# cableVGA.net
KiCad netlist of a schematic drawn in EAGLE
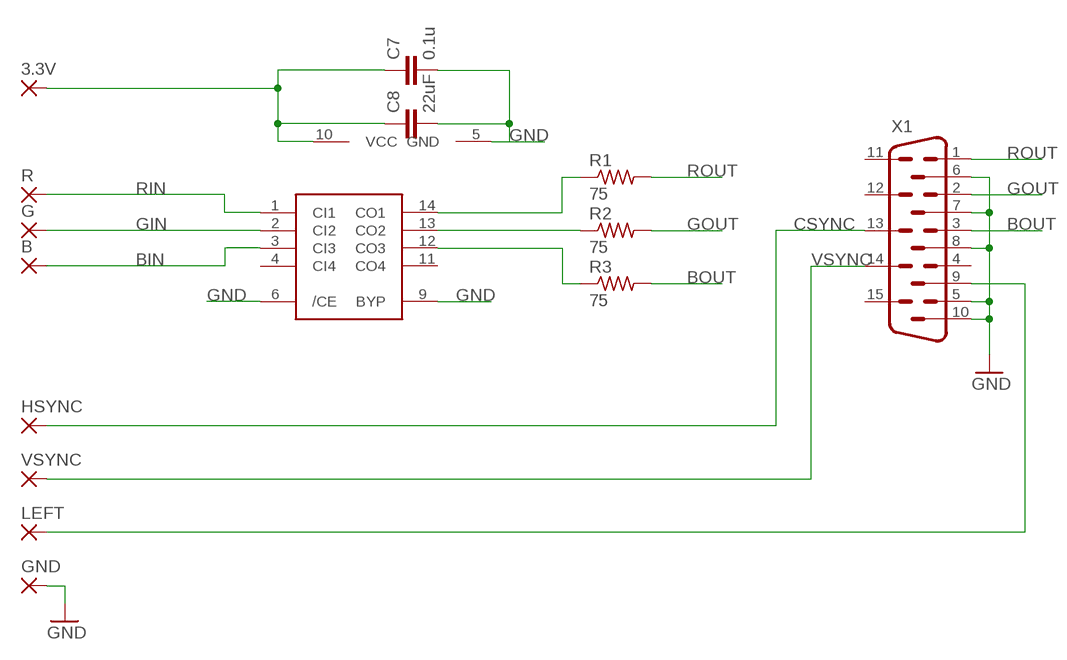
[diagram p0: schematic, sheet 1]

(export (version "E")
  (design (tool "Eeschema 10.0.6"))
  (components
    (comp (ref "3.3V")
      (value "WIREPADSMD2,54-5,08")
      (footprint "eagle-import:SMD2,54-5,08")
      (libsource (lib "eagle-import") (part "WIREPADSMD2,54-5,08"))
    )
    (comp (ref "B")
      (value "WIREPADSMD2,54-5,08")
      (footprint "eagle-import:SMD2,54-5,08")
      (libsource (lib "eagle-import") (part "WIREPADSMD2,54-5,08"))
    )
    (comp (ref "C7")
      (value "0.1u")
      (footprint "eagle-import:C0805K")
      (libsource (lib "eagle-import") (part "C-EUC0805K"))
    )
    (comp (ref "C8")
      (value "22uF")
      (footprint "eagle-import:C0805K")
      (libsource (lib "eagle-import") (part "C-EUC0805K"))
    )
    (comp (ref "G")
      (value "WIREPADSMD2,54-5,08")
      (footprint "eagle-import:SMD2,54-5,08")
      (libsource (lib "eagle-import") (part "WIREPADSMD2,54-5,08"))
    )
    (comp (ref "GND")
      (value "WIREPADSMD2,54-5,08")
      (footprint "eagle-import:SMD2,54-5,08")
      (libsource (lib "eagle-import") (part "WIREPADSMD2,54-5,08"))
    )
    (comp (ref "HSYNC")
      (value "WIREPADSMD2,54-5,08")
      (footprint "eagle-import:SMD2,54-5,08")
      (libsource (lib "eagle-import") (part "WIREPADSMD2,54-5,08"))
    )
    (comp (ref "LEFT")
      (value "WIREPADSMD2,54-5,08")
      (footprint "eagle-import:SMD2,54-5,08")
      (libsource (lib "eagle-import") (part "WIREPADSMD2,54-5,08"))
    )
    (comp (ref "R")
      (value "WIREPADSMD2,54-5,08")
      (footprint "eagle-import:SMD2,54-5,08")
      (libsource (lib "eagle-import") (part "WIREPADSMD2,54-5,08"))
    )
    (comp (ref "R1")
      (value "75")
      (footprint "eagle-import:R0805")
      (libsource (lib "eagle-import") (part "R-US_R0805"))
    )
    (comp (ref "R2")
      (value "75")
      (footprint "eagle-import:R0805")
      (libsource (lib "eagle-import") (part "R-US_R0805"))
    )
    (comp (ref "R3")
      (value "75")
      (footprint "eagle-import:R0805")
      (libsource (lib "eagle-import") (part "R-US_R0805"))
    )
    (comp (ref "U$2")
      (value "THS7374")
      (footprint "eagle-import:THS7374")
      (libsource (lib "eagle-import") (part "THS7374"))
    )
    (comp (ref "VSYNC")
      (value "WIREPADSMD2,54-5,08")
      (footprint "eagle-import:SMD2,54-5,08")
      (libsource (lib "eagle-import") (part "WIREPADSMD2,54-5,08"))
    )
    (comp (ref "X1")
      (value "HM15H")
      (footprint "eagle-import:HDM15H")
      (libsource (lib "eagle-import") (part "HM15H"))
    )
  )
  (nets
    (net (code "1") (name "/BIN") (class "Default")
      (node (ref "B") (pin "1") (pinfunction "P_1") (pintype "passive"))
      (node (ref "U$2") (pin "3") (pinfunction "CI3_3") (pintype "bidirectional"))
    )
    (net (code "2") (name "/BOUT") (class "Default")
      (node (ref "R3") (pin "2") (pinfunction "2_2") (pintype "passive"))
      (node (ref "X1") (pin "3") (pinfunction "3_3") (pintype "passive"))
    )
    (net (code "3") (name "/CSYNC") (class "Default")
      (node (ref "HSYNC") (pin "1") (pinfunction "P_1") (pintype "passive"))
      (node (ref "X1") (pin "13") (pinfunction "13_13") (pintype "passive"))
    )
    (net (code "4") (name "/GIN") (class "Default")
      (node (ref "G") (pin "1") (pinfunction "P_1") (pintype "passive"))
      (node (ref "U$2") (pin "2") (pinfunction "CI2_2") (pintype "bidirectional"))
    )
    (net (code "5") (name "/GOUT") (class "Default")
      (node (ref "R2") (pin "2") (pinfunction "2_2") (pintype "passive"))
      (node (ref "X1") (pin "2") (pinfunction "2_2") (pintype "passive"))
    )
    (net (code "6") (name "/RIN") (class "Default")
      (node (ref "R") (pin "1") (pinfunction "P_1") (pintype "passive"))
      (node (ref "U$2") (pin "1") (pinfunction "CI1_1") (pintype "bidirectional"))
    )
    (net (code "7") (name "/ROUT") (class "Default")
      (node (ref "R1") (pin "2") (pinfunction "2_2") (pintype "passive"))
      (node (ref "X1") (pin "1") (pinfunction "1_1") (pintype "passive"))
    )
    (net (code "8") (name "/VSYNC") (class "Default")
      (node (ref "VSYNC") (pin "1") (pinfunction "P_1") (pintype "passive"))
      (node (ref "X1") (pin "14") (pinfunction "14_14") (pintype "passive"))
    )
    (net (code "9") (name "GND") (class "Default")
      (node (ref "C7") (pin "2") (pinfunction "2_2") (pintype "passive"))
      (node (ref "C8") (pin "2") (pinfunction "2_2") (pintype "passive"))
      (node (ref "GND") (pin "1") (pinfunction "P_1") (pintype "passive"))
      (node (ref "U$2") (pin "5") (pinfunction "GND_5") (pintype "bidirectional"))
      (node (ref "U$2") (pin "6") (pinfunction "/CE_6") (pintype "bidirectional"))
      (node (ref "U$2") (pin "9") (pinfunction "BYP_9") (pintype "bidirectional"))
      (node (ref "X1") (pin "10") (pinfunction "10_10") (pintype "passive"))
      (node (ref "X1") (pin "5") (pinfunction "5_5") (pintype "passive"))
      (node (ref "X1") (pin "6") (pinfunction "6_6") (pintype "passive"))
      (node (ref "X1") (pin "7") (pinfunction "7_7") (pintype "passive"))
      (node (ref "X1") (pin "8") (pinfunction "8_8") (pintype "passive"))
    )
    (net (code "10") (name "Net-(3.3V-P)") (class "Default")
      (node (ref "3.3V") (pin "1") (pinfunction "P_1") (pintype "passive"))
      (node (ref "C7") (pin "1") (pinfunction "1_1") (pintype "passive"))
      (node (ref "C8") (pin "1") (pinfunction "1_1") (pintype "passive"))
      (node (ref "U$2") (pin "10") (pinfunction "VCC_10") (pintype "bidirectional"))
    )
    (net (code "11") (name "Net-(LEFT-P)") (class "Default")
      (node (ref "LEFT") (pin "1") (pinfunction "P_1") (pintype "passive"))
      (node (ref "X1") (pin "9") (pinfunction "9_9") (pintype "passive"))
    )
    (net (code "12") (name "Net-(U$2A-CO1)") (class "Default")
      (node (ref "R1") (pin "1") (pinfunction "1_1") (pintype "passive"))
      (node (ref "U$2") (pin "14") (pinfunction "CO1_14") (pintype "bidirectional"))
    )
    (net (code "13") (name "Net-(U$2A-CO2)") (class "Default")
      (node (ref "R2") (pin "1") (pinfunction "1_1") (pintype "passive"))
      (node (ref "U$2") (pin "13") (pinfunction "CO2_13") (pintype "bidirectional"))
    )
    (net (code "14") (name "Net-(U$2A-CO3)") (class "Default")
      (node (ref "R3") (pin "1") (pinfunction "1_1") (pintype "passive"))
      (node (ref "U$2") (pin "12") (pinfunction "CO3_12") (pintype "bidirectional"))
    )
    (net (code "15") (name "unconnected-(U$2A-CI4-Pad4)") (class "Default")
      (node (ref "U$2") (pin "4") (pinfunction "CI4_4") (pintype "bidirectional"))
    )
    (net (code "16") (name "unconnected-(U$2A-CO4-Pad11)") (class "Default")
      (node (ref "U$2") (pin "11") (pinfunction "CO4_11") (pintype "bidirectional"))
    )
    (net (code "17") (name "unconnected-(X1-Pad4)") (class "Default")
      (node (ref "X1") (pin "4") (pinfunction "4_4") (pintype "passive"))
    )
    (net (code "18") (name "unconnected-(X1-Pad11)") (class "Default")
      (node (ref "X1") (pin "11") (pinfunction "11_11") (pintype "passive"))
    )
    (net (code "19") (name "unconnected-(X1-Pad12)") (class "Default")
      (node (ref "X1") (pin "12") (pinfunction "12_12") (pintype "passive"))
    )
    (net (code "20") (name "unconnected-(X1-Pad15)") (class "Default")
      (node (ref "X1") (pin "15") (pinfunction "15_15") (pintype "passive"))
    )
  )
)
